# interstage_B1v2.net
KiCad netlist of a schematic drawn in EAGLE
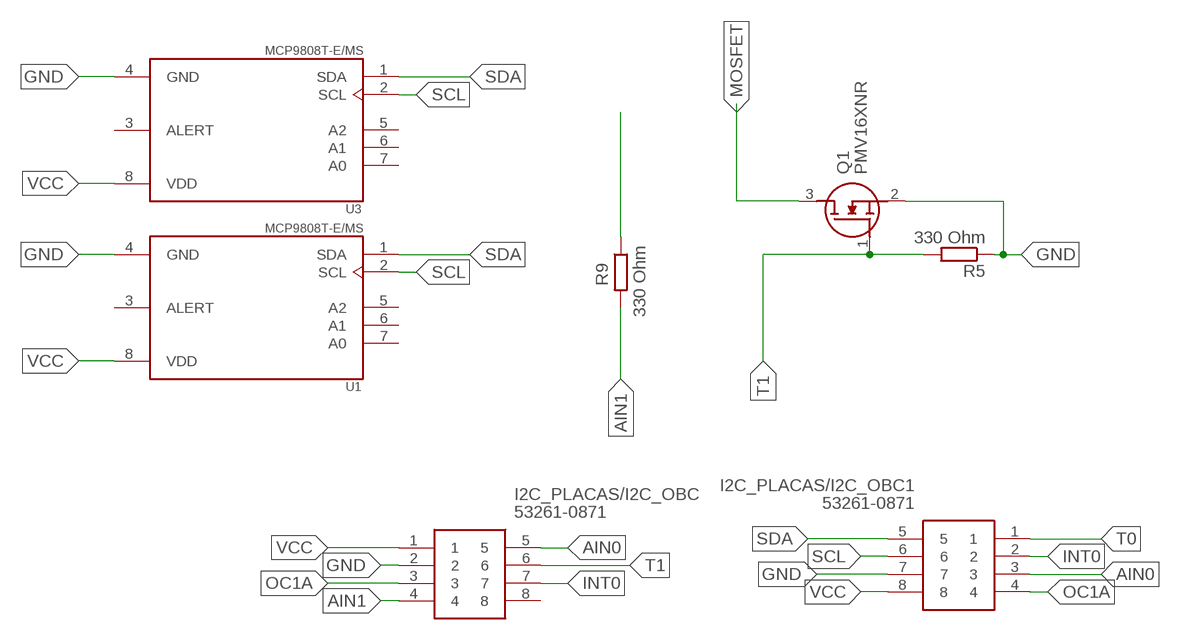
[diagram p0: schematic, sheet 1]

(export (version "E")
  (design (tool "Eeschema 10.0.6"))
  (components
    (comp (ref "I2C_PLACAS/I2C_OBC")
      (value "53261-0871")
      (footprint "eagle-import:53261-0871")
      (fields (field (name "MOUSER_PART_NUMBER") "538-53261-0871"))
      (libsource (lib "eagle-import") (part "53261-0871"))
    )
    (comp (ref "I2C_PLACAS/I2C_OBC1")
      (value "53261-0871")
      (footprint "eagle-import:53261-0871")
      (fields (field (name "MOUSER_PART_NUMBER") "538-53261-0871"))
      (libsource (lib "eagle-import") (part "53261-0871"))
    )
    (comp (ref "Q1")
      (value "PMV16XNR")
      (footprint "eagle-import:SOT95P230X110-3N")
      (fields (field (name "MOUSER_PART_NUMBER") "771-PMV16XNR"))
      (libsource (lib "eagle-import") (part "PMV16XNR"))
    )
    (comp (ref "R5")
      (value "330 Ohm")
      (footprint "eagle-import:R1206")
      (libsource (lib "eagle-import") (part "R-EU_R1206"))
    )
    (comp (ref "R9")
      (value "330 Ohm")
      (footprint "eagle-import:R1206")
      (libsource (lib "eagle-import") (part "R-EU_R1206"))
    )
    (comp (ref "U1")
      (value "MCP9808T-E/MS")
      (footprint "eagle-import:SOP65P490X110-8N")
      (fields (field (name "DIGI-KEY_PART_NUMBER") "MCP9808T-E/MSCT-ND") (field (name "MF") "Microchip"))
      (libsource (lib "eagle-import") (part "MCP9808T-E/MS"))
    )
    (comp (ref "U3")
      (value "MCP9808T-E/MS")
      (footprint "eagle-import:SOP65P490X110-8N")
      (fields (field (name "DIGI-KEY_PART_NUMBER") "MCP9808T-E/MSCT-ND") (field (name "MF") "Microchip"))
      (libsource (lib "eagle-import") (part "MCP9808T-E/MS"))
    )
  )
  (nets
    (net (code "1") (name "AIN0") (class "Default")
      (node (ref "I2C_PLACAS/I2C_OBC") (pin "5") (pinfunction "5_5") (pintype "bidirectional"))
      (node (ref "I2C_PLACAS/I2C_OBC1") (pin "3") (pinfunction "3_3") (pintype "bidirectional"))
    )
    (net (code "2") (name "AIN1") (class "Default")
      (node (ref "I2C_PLACAS/I2C_OBC") (pin "4") (pinfunction "4_4") (pintype "bidirectional"))
      (node (ref "R9") (pin "2") (pinfunction "2_2") (pintype "passive"))
    )
    (net (code "3") (name "GND") (class "Default")
      (node (ref "I2C_PLACAS/I2C_OBC") (pin "2") (pinfunction "2_2") (pintype "bidirectional"))
      (node (ref "I2C_PLACAS/I2C_OBC1") (pin "7") (pinfunction "7_7") (pintype "bidirectional"))
      (node (ref "Q1") (pin "2") (pinfunction "S_2") (pintype "bidirectional"))
      (node (ref "R5") (pin "1") (pinfunction "1_1") (pintype "passive"))
      (node (ref "U1") (pin "4") (pinfunction "GND_4") (pintype "power_in"))
      (node (ref "U3") (pin "4") (pinfunction "GND_4") (pintype "power_in"))
    )
    (net (code "4") (name "INT0") (class "Default")
      (node (ref "I2C_PLACAS/I2C_OBC") (pin "7") (pinfunction "7_7") (pintype "bidirectional"))
      (node (ref "I2C_PLACAS/I2C_OBC1") (pin "2") (pinfunction "2_2") (pintype "bidirectional"))
    )
    (net (code "5") (name "MOSFET") (class "Default")
      (node (ref "Q1") (pin "3") (pinfunction "D_3") (pintype "bidirectional"))
    )
    (net (code "6") (name "OC1A") (class "Default")
      (node (ref "I2C_PLACAS/I2C_OBC") (pin "3") (pinfunction "3_3") (pintype "bidirectional"))
      (node (ref "I2C_PLACAS/I2C_OBC1") (pin "4") (pinfunction "4_4") (pintype "bidirectional"))
    )
    (net (code "7") (name "SCL") (class "Default")
      (node (ref "I2C_PLACAS/I2C_OBC1") (pin "6") (pinfunction "6_6") (pintype "bidirectional"))
      (node (ref "U1") (pin "2") (pinfunction "SCL_2") (pintype "input"))
      (node (ref "U3") (pin "2") (pinfunction "SCL_2") (pintype "input"))
    )
    (net (code "8") (name "SDA") (class "Default")
      (node (ref "I2C_PLACAS/I2C_OBC1") (pin "5") (pinfunction "5_5") (pintype "bidirectional"))
      (node (ref "U1") (pin "1") (pinfunction "SDA_1") (pintype "bidirectional"))
      (node (ref "U3") (pin "1") (pinfunction "SDA_1") (pintype "bidirectional"))
    )
    (net (code "9") (name "T0") (class "Default")
      (node (ref "I2C_PLACAS/I2C_OBC1") (pin "1") (pinfunction "1_1") (pintype "bidirectional"))
    )
    (net (code "10") (name "T1") (class "Default")
      (node (ref "I2C_PLACAS/I2C_OBC") (pin "6") (pinfunction "6_6") (pintype "bidirectional"))
      (node (ref "Q1") (pin "1") (pinfunction "G_1") (pintype "bidirectional"))
      (node (ref "R5") (pin "2") (pinfunction "2_2") (pintype "passive"))
    )
    (net (code "11") (name "VCC") (class "Default")
      (node (ref "I2C_PLACAS/I2C_OBC") (pin "1") (pinfunction "1_1") (pintype "bidirectional"))
      (node (ref "I2C_PLACAS/I2C_OBC1") (pin "8") (pinfunction "8_8") (pintype "bidirectional"))
      (node (ref "U1") (pin "8") (pinfunction "VDD_8") (pintype "power_in"))
      (node (ref "U3") (pin "8") (pinfunction "VDD_8") (pintype "power_in"))
    )
    (net (code "12") (name "unconnected-(I2C_PLACAS/I2C_OBC-Pad8)") (class "Default")
      (node (ref "I2C_PLACAS/I2C_OBC") (pin "8") (pinfunction "8_8") (pintype "bidirectional"))
    )
    (net (code "13") (name "unconnected-(R9-Pad1)") (class "Default")
      (node (ref "R9") (pin "1") (pinfunction "1_1") (pintype "passive"))
    )
    (net (code "14") (name "unconnected-(U1-A0-Pad7)") (class "Default")
      (node (ref "U1") (pin "7") (pinfunction "A0_7") (pintype "input"))
    )
    (net (code "15") (name "unconnected-(U1-A1-Pad6)") (class "Default")
      (node (ref "U1") (pin "6") (pinfunction "A1_6") (pintype "input"))
    )
    (net (code "16") (name "unconnected-(U1-A2-Pad5)") (class "Default")
      (node (ref "U1") (pin "5") (pinfunction "A2_5") (pintype "input"))
    )
    (net (code "17") (name "unconnected-(U1-ALERT-Pad3)") (class "Default")
      (node (ref "U1") (pin "3") (pinfunction "ALERT_3") (pintype "output"))
    )
    (net (code "18") (name "unconnected-(U3-A0-Pad7)") (class "Default")
      (node (ref "U3") (pin "7") (pinfunction "A0_7") (pintype "input"))
    )
    (net (code "19") (name "unconnected-(U3-A1-Pad6)") (class "Default")
      (node (ref "U3") (pin "6") (pinfunction "A1_6") (pintype "input"))
    )
    (net (code "20") (name "unconnected-(U3-A2-Pad5)") (class "Default")
      (node (ref "U3") (pin "5") (pinfunction "A2_5") (pintype "input"))
    )
    (net (code "21") (name "unconnected-(U3-ALERT-Pad3)") (class "Default")
      (node (ref "U3") (pin "3") (pinfunction "ALERT_3") (pintype "output"))
    )
  )
)
